# ACC.net
KiCad netlist of a schematic drawn in EAGLE
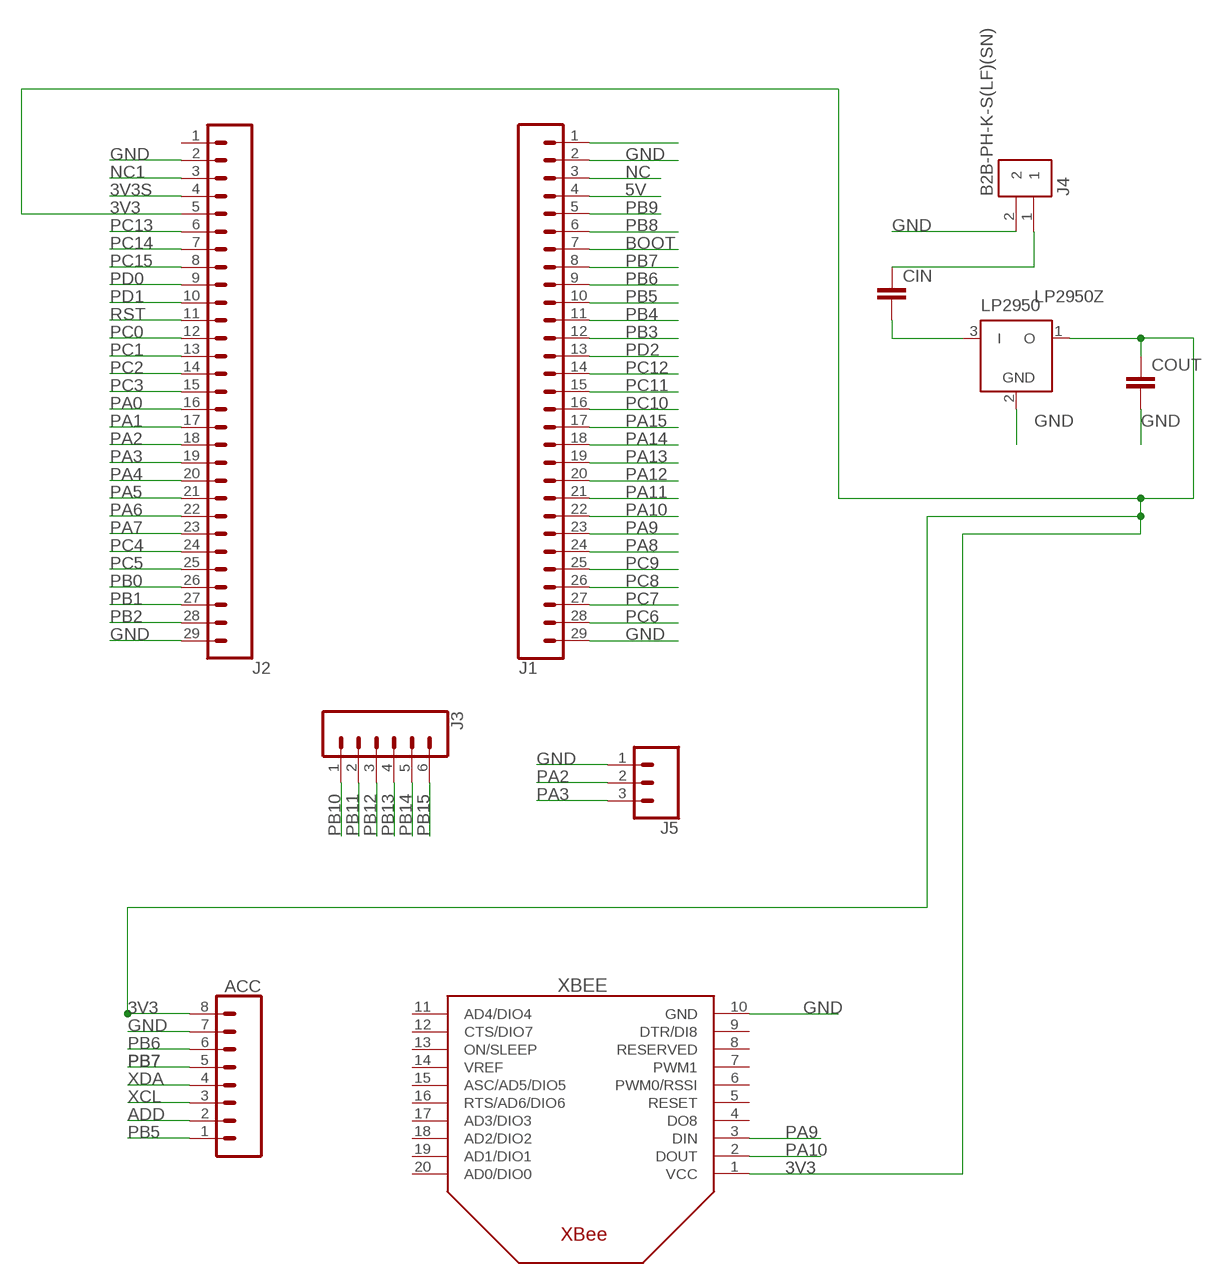
[diagram p0: schematic, sheet 1]

(export (version "E")
  (design (tool "Eeschema 10.0.6"))
  (components
    (comp (ref "ACC")
      (value "CONN_08\"")
      (footprint "eagle-import:1X08")
      (libsource (lib "eagle-import") (part "CONN_08{dblquote}"))
    )
    (comp (ref "CIN")
      (value "C2,5-3")
      (footprint "eagle-import:C2.5-3")
      (libsource (lib "eagle-import") (part "C2,5-3"))
    )
    (comp (ref "COUT")
      (value "C2,5-3")
      (footprint "eagle-import:C2.5-3")
      (libsource (lib "eagle-import") (part "C2,5-3"))
    )
    (comp (ref "J1")
      (value "CONN_29")
      (footprint "eagle-import:1X29")
      (libsource (lib "eagle-import") (part "CONN_29"))
    )
    (comp (ref "J2")
      (value "CONN_29")
      (footprint "eagle-import:1X29")
      (libsource (lib "eagle-import") (part "CONN_29"))
    )
    (comp (ref "J3")
      (value "CONN_06SILK_FEMALE_PTH")
      (footprint "eagle-import:1X06")
      (libsource (lib "eagle-import") (part "CONN_06SILK_FEMALE_PTH"))
    )
    (comp (ref "J4")
      (value "B2B-PH-K-S(LF)(SN)")
      (footprint "eagle-import:JST_B2B-PH-K-S(LF)(SN)")
      (fields
        (field (name "DIGI-KEY_PART_NUMBER") "455-1704-ND")
        (field (name "MF") "JST Sales")
        (field (name "MP") "B2B-PH-K-S_LF__SN_")
      )
      (libsource (lib "eagle-import") (part "B2B-PH-K-S(LF)(SN)"))
    )
    (comp (ref "J5")
      (value "CONN_03")
      (footprint "eagle-import:1X03")
      (libsource (lib "eagle-import") (part "CONN_03"))
    )
    (comp (ref "LP2950")
      (value "LP2950Z")
      (footprint "eagle-import:TO92")
      (libsource (lib "eagle-import") (part "LP2950Z"))
    )
    (comp (ref "XBEE")
      (value "XBEE")
      (footprint "eagle-import:XBEE")
      (libsource (lib "eagle-import") (part "XBEE"))
    )
  )
  (nets
    (net (code "1") (name "/3V3") (class "Default")
      (node (ref "ACC") (pin "8") (pinfunction "8_8") (pintype "passive"))
      (node (ref "COUT") (pin "1") (pinfunction "1_1") (pintype "passive"))
      (node (ref "J2") (pin "5") (pinfunction "5_5") (pintype "passive"))
      (node (ref "LP2950") (pin "1") (pinfunction "O_1") (pintype "input"))
      (node (ref "XBEE") (pin "1") (pinfunction "VCC_1") (pintype "power_in"))
    )
    (net (code "2") (name "/3V3S") (class "Default")
      (node (ref "J2") (pin "4") (pinfunction "4_4") (pintype "passive"))
    )
    (net (code "3") (name "/5V") (class "Default")
      (node (ref "J1") (pin "4") (pinfunction "4_4") (pintype "passive"))
    )
    (net (code "4") (name "/ADD") (class "Default")
      (node (ref "ACC") (pin "2") (pinfunction "2_2") (pintype "passive"))
    )
    (net (code "5") (name "/BOOT") (class "Default")
      (node (ref "J1") (pin "7") (pinfunction "7_7") (pintype "passive"))
    )
    (net (code "6") (name "/GND") (class "Default")
      (node (ref "ACC") (pin "7") (pinfunction "7_7") (pintype "passive"))
      (node (ref "COUT") (pin "2") (pinfunction "2_2") (pintype "passive"))
      (node (ref "J1") (pin "2") (pinfunction "2_2") (pintype "passive"))
      (node (ref "J1") (pin "29") (pinfunction "29_29") (pintype "passive"))
      (node (ref "J2") (pin "2") (pinfunction "2_2") (pintype "passive"))
      (node (ref "J2") (pin "29") (pinfunction "29_29") (pintype "passive"))
      (node (ref "J4") (pin "2") (pinfunction "2_2") (pintype "passive"))
      (node (ref "J5") (pin "1") (pinfunction "1_1") (pintype "passive"))
      (node (ref "LP2950") (pin "2") (pinfunction "GND_2") (pintype "power_in"))
      (node (ref "XBEE") (pin "10") (pinfunction "GND_10") (pintype "power_in"))
    )
    (net (code "7") (name "/NC") (class "Default")
      (node (ref "J1") (pin "3") (pinfunction "3_3") (pintype "passive"))
    )
    (net (code "8") (name "/NC1") (class "Default")
      (node (ref "J2") (pin "3") (pinfunction "3_3") (pintype "passive"))
    )
    (net (code "9") (name "/PA0") (class "Default")
      (node (ref "J2") (pin "16") (pinfunction "16_16") (pintype "passive"))
    )
    (net (code "10") (name "/PA1") (class "Default")
      (node (ref "J2") (pin "17") (pinfunction "17_17") (pintype "passive"))
    )
    (net (code "11") (name "/PA2") (class "Default")
      (node (ref "J2") (pin "18") (pinfunction "18_18") (pintype "passive"))
      (node (ref "J5") (pin "2") (pinfunction "2_2") (pintype "passive"))
    )
    (net (code "12") (name "/PA3") (class "Default")
      (node (ref "J2") (pin "19") (pinfunction "19_19") (pintype "passive"))
      (node (ref "J5") (pin "3") (pinfunction "3_3") (pintype "passive"))
    )
    (net (code "13") (name "/PA4") (class "Default")
      (node (ref "J2") (pin "20") (pinfunction "20_20") (pintype "passive"))
    )
    (net (code "14") (name "/PA5") (class "Default")
      (node (ref "J2") (pin "21") (pinfunction "21_21") (pintype "passive"))
    )
    (net (code "15") (name "/PA6") (class "Default")
      (node (ref "J2") (pin "22") (pinfunction "22_22") (pintype "passive"))
    )
    (net (code "16") (name "/PA7") (class "Default")
      (node (ref "J2") (pin "23") (pinfunction "23_23") (pintype "passive"))
    )
    (net (code "17") (name "/PA8") (class "Default")
      (node (ref "J1") (pin "24") (pinfunction "24_24") (pintype "passive"))
    )
    (net (code "18") (name "/PA9") (class "Default")
      (node (ref "J1") (pin "23") (pinfunction "23_23") (pintype "passive"))
      (node (ref "XBEE") (pin "3") (pinfunction "DIN_3") (pintype "input"))
    )
    (net (code "19") (name "/PA10") (class "Default")
      (node (ref "J1") (pin "22") (pinfunction "22_22") (pintype "passive"))
      (node (ref "XBEE") (pin "2") (pinfunction "DOUT_2") (pintype "output"))
    )
    (net (code "20") (name "/PA11") (class "Default")
      (node (ref "J1") (pin "21") (pinfunction "21_21") (pintype "passive"))
    )
    (net (code "21") (name "/PA12") (class "Default")
      (node (ref "J1") (pin "20") (pinfunction "20_20") (pintype "passive"))
    )
    (net (code "22") (name "/PA13") (class "Default")
      (node (ref "J1") (pin "19") (pinfunction "19_19") (pintype "passive"))
    )
    (net (code "23") (name "/PA14") (class "Default")
      (node (ref "J1") (pin "18") (pinfunction "18_18") (pintype "passive"))
    )
    (net (code "24") (name "/PA15") (class "Default")
      (node (ref "J1") (pin "17") (pinfunction "17_17") (pintype "passive"))
    )
    (net (code "25") (name "/PB0") (class "Default")
      (node (ref "J2") (pin "26") (pinfunction "26_26") (pintype "passive"))
    )
    (net (code "26") (name "/PB1") (class "Default")
      (node (ref "J2") (pin "27") (pinfunction "27_27") (pintype "passive"))
    )
    (net (code "27") (name "/PB2") (class "Default")
      (node (ref "J2") (pin "28") (pinfunction "28_28") (pintype "passive"))
    )
    (net (code "28") (name "/PB3") (class "Default")
      (node (ref "J1") (pin "12") (pinfunction "12_12") (pintype "passive"))
    )
    (net (code "29") (name "/PB4") (class "Default")
      (node (ref "J1") (pin "11") (pinfunction "11_11") (pintype "passive"))
    )
    (net (code "30") (name "/PB5") (class "Default")
      (node (ref "ACC") (pin "1") (pinfunction "1_1") (pintype "passive"))
      (node (ref "J1") (pin "10") (pinfunction "10_10") (pintype "passive"))
    )
    (net (code "31") (name "/PB6") (class "Default")
      (node (ref "ACC") (pin "6") (pinfunction "6_6") (pintype "passive"))
      (node (ref "J1") (pin "9") (pinfunction "9_9") (pintype "passive"))
    )
    (net (code "32") (name "/PB7") (class "Default")
      (node (ref "ACC") (pin "5") (pinfunction "5_5") (pintype "passive"))
      (node (ref "J1") (pin "8") (pinfunction "8_8") (pintype "passive"))
    )
    (net (code "33") (name "/PB8") (class "Default")
      (node (ref "J1") (pin "6") (pinfunction "6_6") (pintype "passive"))
    )
    (net (code "34") (name "/PB9") (class "Default")
      (node (ref "J1") (pin "5") (pinfunction "5_5") (pintype "passive"))
    )
    (net (code "35") (name "/PB10") (class "Default")
      (node (ref "J3") (pin "1") (pinfunction "1_1") (pintype "passive"))
    )
    (net (code "36") (name "/PB11") (class "Default")
      (node (ref "J3") (pin "2") (pinfunction "2_2") (pintype "passive"))
    )
    (net (code "37") (name "/PB12") (class "Default")
      (node (ref "J3") (pin "3") (pinfunction "3_3") (pintype "passive"))
    )
    (net (code "38") (name "/PB13") (class "Default")
      (node (ref "J3") (pin "4") (pinfunction "4_4") (pintype "passive"))
    )
    (net (code "39") (name "/PB14") (class "Default")
      (node (ref "J3") (pin "5") (pinfunction "5_5") (pintype "passive"))
    )
    (net (code "40") (name "/PB15") (class "Default")
      (node (ref "J3") (pin "6") (pinfunction "6_6") (pintype "passive"))
    )
    (net (code "41") (name "/PC0") (class "Default")
      (node (ref "J2") (pin "12") (pinfunction "12_12") (pintype "passive"))
    )
    (net (code "42") (name "/PC1") (class "Default")
      (node (ref "J2") (pin "13") (pinfunction "13_13") (pintype "passive"))
    )
    (net (code "43") (name "/PC2") (class "Default")
      (node (ref "J2") (pin "14") (pinfunction "14_14") (pintype "passive"))
    )
    (net (code "44") (name "/PC3") (class "Default")
      (node (ref "J2") (pin "15") (pinfunction "15_15") (pintype "passive"))
    )
    (net (code "45") (name "/PC4") (class "Default")
      (node (ref "J2") (pin "24") (pinfunction "24_24") (pintype "passive"))
    )
    (net (code "46") (name "/PC5") (class "Default")
      (node (ref "J2") (pin "25") (pinfunction "25_25") (pintype "passive"))
    )
    (net (code "47") (name "/PC6") (class "Default")
      (node (ref "J1") (pin "28") (pinfunction "28_28") (pintype "passive"))
    )
    (net (code "48") (name "/PC7") (class "Default")
      (node (ref "J1") (pin "27") (pinfunction "27_27") (pintype "passive"))
    )
    (net (code "49") (name "/PC8") (class "Default")
      (node (ref "J1") (pin "26") (pinfunction "26_26") (pintype "passive"))
    )
    (net (code "50") (name "/PC9") (class "Default")
      (node (ref "J1") (pin "25") (pinfunction "25_25") (pintype "passive"))
    )
    (net (code "51") (name "/PC10") (class "Default")
      (node (ref "J1") (pin "16") (pinfunction "16_16") (pintype "passive"))
    )
    (net (code "52") (name "/PC11") (class "Default")
      (node (ref "J1") (pin "15") (pinfunction "15_15") (pintype "passive"))
    )
    (net (code "53") (name "/PC12") (class "Default")
      (node (ref "J1") (pin "14") (pinfunction "14_14") (pintype "passive"))
    )
    (net (code "54") (name "/PC13") (class "Default")
      (node (ref "J2") (pin "6") (pinfunction "6_6") (pintype "passive"))
    )
    (net (code "55") (name "/PC14") (class "Default")
      (node (ref "J2") (pin "7") (pinfunction "7_7") (pintype "passive"))
    )
    (net (code "56") (name "/PC15") (class "Default")
      (node (ref "J2") (pin "8") (pinfunction "8_8") (pintype "passive"))
    )
    (net (code "57") (name "/PD0") (class "Default")
      (node (ref "J2") (pin "9") (pinfunction "9_9") (pintype "passive"))
    )
    (net (code "58") (name "/PD1") (class "Default")
      (node (ref "J2") (pin "10") (pinfunction "10_10") (pintype "passive"))
    )
    (net (code "59") (name "/PD2") (class "Default")
      (node (ref "J1") (pin "13") (pinfunction "13_13") (pintype "passive"))
    )
    (net (code "60") (name "/RST") (class "Default")
      (node (ref "J2") (pin "11") (pinfunction "11_11") (pintype "passive"))
    )
    (net (code "61") (name "/XCL") (class "Default")
      (node (ref "ACC") (pin "3") (pinfunction "3_3") (pintype "passive"))
    )
    (net (code "62") (name "/XDA") (class "Default")
      (node (ref "ACC") (pin "4") (pinfunction "4_4") (pintype "passive"))
    )
    (net (code "63") (name "Net-(CIN-Pad1)") (class "Default")
      (node (ref "CIN") (pin "1") (pinfunction "1_1") (pintype "passive"))
      (node (ref "J4") (pin "1") (pinfunction "1_1") (pintype "passive"))
    )
    (net (code "64") (name "Net-(LP2950-I)") (class "Default")
      (node (ref "CIN") (pin "2") (pinfunction "2_2") (pintype "passive"))
      (node (ref "LP2950") (pin "3") (pinfunction "I_3") (pintype "input"))
    )
    (net (code "65") (name "unconnected-(J1-Pad1)") (class "Default")
      (node (ref "J1") (pin "1") (pinfunction "1_1") (pintype "passive"))
    )
    (net (code "66") (name "unconnected-(J2-Pad1)") (class "Default")
      (node (ref "J2") (pin "1") (pinfunction "1_1") (pintype "passive"))
    )
    (net (code "67") (name "unconnected-(XBEE-AD0{slash}DIO0-Pad20)") (class "Default")
      (node (ref "XBEE") (pin "20") (pinfunction "AD0/DIO0_20") (pintype "bidirectional"))
    )
    (net (code "68") (name "unconnected-(XBEE-AD1{slash}DIO1-Pad19)") (class "Default")
      (node (ref "XBEE") (pin "19") (pinfunction "AD1/DIO1_19") (pintype "bidirectional"))
    )
    (net (code "69") (name "unconnected-(XBEE-AD2{slash}DIO2-Pad18)") (class "Default")
      (node (ref "XBEE") (pin "18") (pinfunction "AD2/DIO2_18") (pintype "bidirectional"))
    )
    (net (code "70") (name "unconnected-(XBEE-AD3{slash}DIO3-Pad17)") (class "Default")
      (node (ref "XBEE") (pin "17") (pinfunction "AD3/DIO3_17") (pintype "bidirectional"))
    )
    (net (code "71") (name "unconnected-(XBEE-AD4{slash}DIO4-Pad11)") (class "Default")
      (node (ref "XBEE") (pin "11") (pinfunction "AD4/DIO4_11") (pintype "bidirectional"))
    )
    (net (code "72") (name "unconnected-(XBEE-ASC{slash}AD5{slash}DIO5-Pad15)") (class "Default")
      (node (ref "XBEE") (pin "15") (pinfunction "ASC/AD5/DIO5_15") (pintype "bidirectional"))
    )
    (net (code "73") (name "unconnected-(XBEE-CTS{slash}DIO7-Pad12)") (class "Default")
      (node (ref "XBEE") (pin "12") (pinfunction "CTS/DIO7_12") (pintype "bidirectional"))
    )
    (net (code "74") (name "unconnected-(XBEE-DO8-Pad4)") (class "Default")
      (node (ref "XBEE") (pin "4") (pinfunction "DO8_4") (pintype "output"))
    )
    (net (code "75") (name "unconnected-(XBEE-DTR{slash}DI8-Pad9)") (class "Default")
      (node (ref "XBEE") (pin "9") (pinfunction "DTR/DI8_9") (pintype "input"))
    )
    (net (code "76") (name "unconnected-(XBEE-ON{slash}SLEEP-Pad13)") (class "Default")
      (node (ref "XBEE") (pin "13") (pinfunction "ON/SLEEP_13") (pintype "output"))
    )
    (net (code "77") (name "unconnected-(XBEE-PWM0{slash}RSSI-Pad6)") (class "Default")
      (node (ref "XBEE") (pin "6") (pinfunction "PWM0/RSSI_6") (pintype "output"))
    )
    (net (code "78") (name "unconnected-(XBEE-PWM1-Pad7)") (class "Default")
      (node (ref "XBEE") (pin "7") (pinfunction "PWM1_7") (pintype "output"))
    )
    (net (code "79") (name "unconnected-(XBEE-RESERVED-Pad8)") (class "Default")
      (node (ref "XBEE") (pin "8") (pinfunction "RESERVED_8") (pintype "no_connect"))
    )
    (net (code "80") (name "unconnected-(XBEE-RESET-Pad5)") (class "Default")
      (node (ref "XBEE") (pin "5") (pinfunction "RESET_5") (pintype "input"))
    )
    (net (code "81") (name "unconnected-(XBEE-RTS{slash}AD6{slash}DIO6-Pad16)") (class "Default")
      (node (ref "XBEE") (pin "16") (pinfunction "RTS/AD6/DIO6_16") (pintype "bidirectional"))
    )
    (net (code "82") (name "unconnected-(XBEE-VREF-Pad14)") (class "Default")
      (node (ref "XBEE") (pin "14") (pinfunction "VREF_14") (pintype "input"))
    )
  )
)
